# wireless-ac-motor-controller-mk-1_2.net
KiCad netlist of a schematic drawn in EAGLE
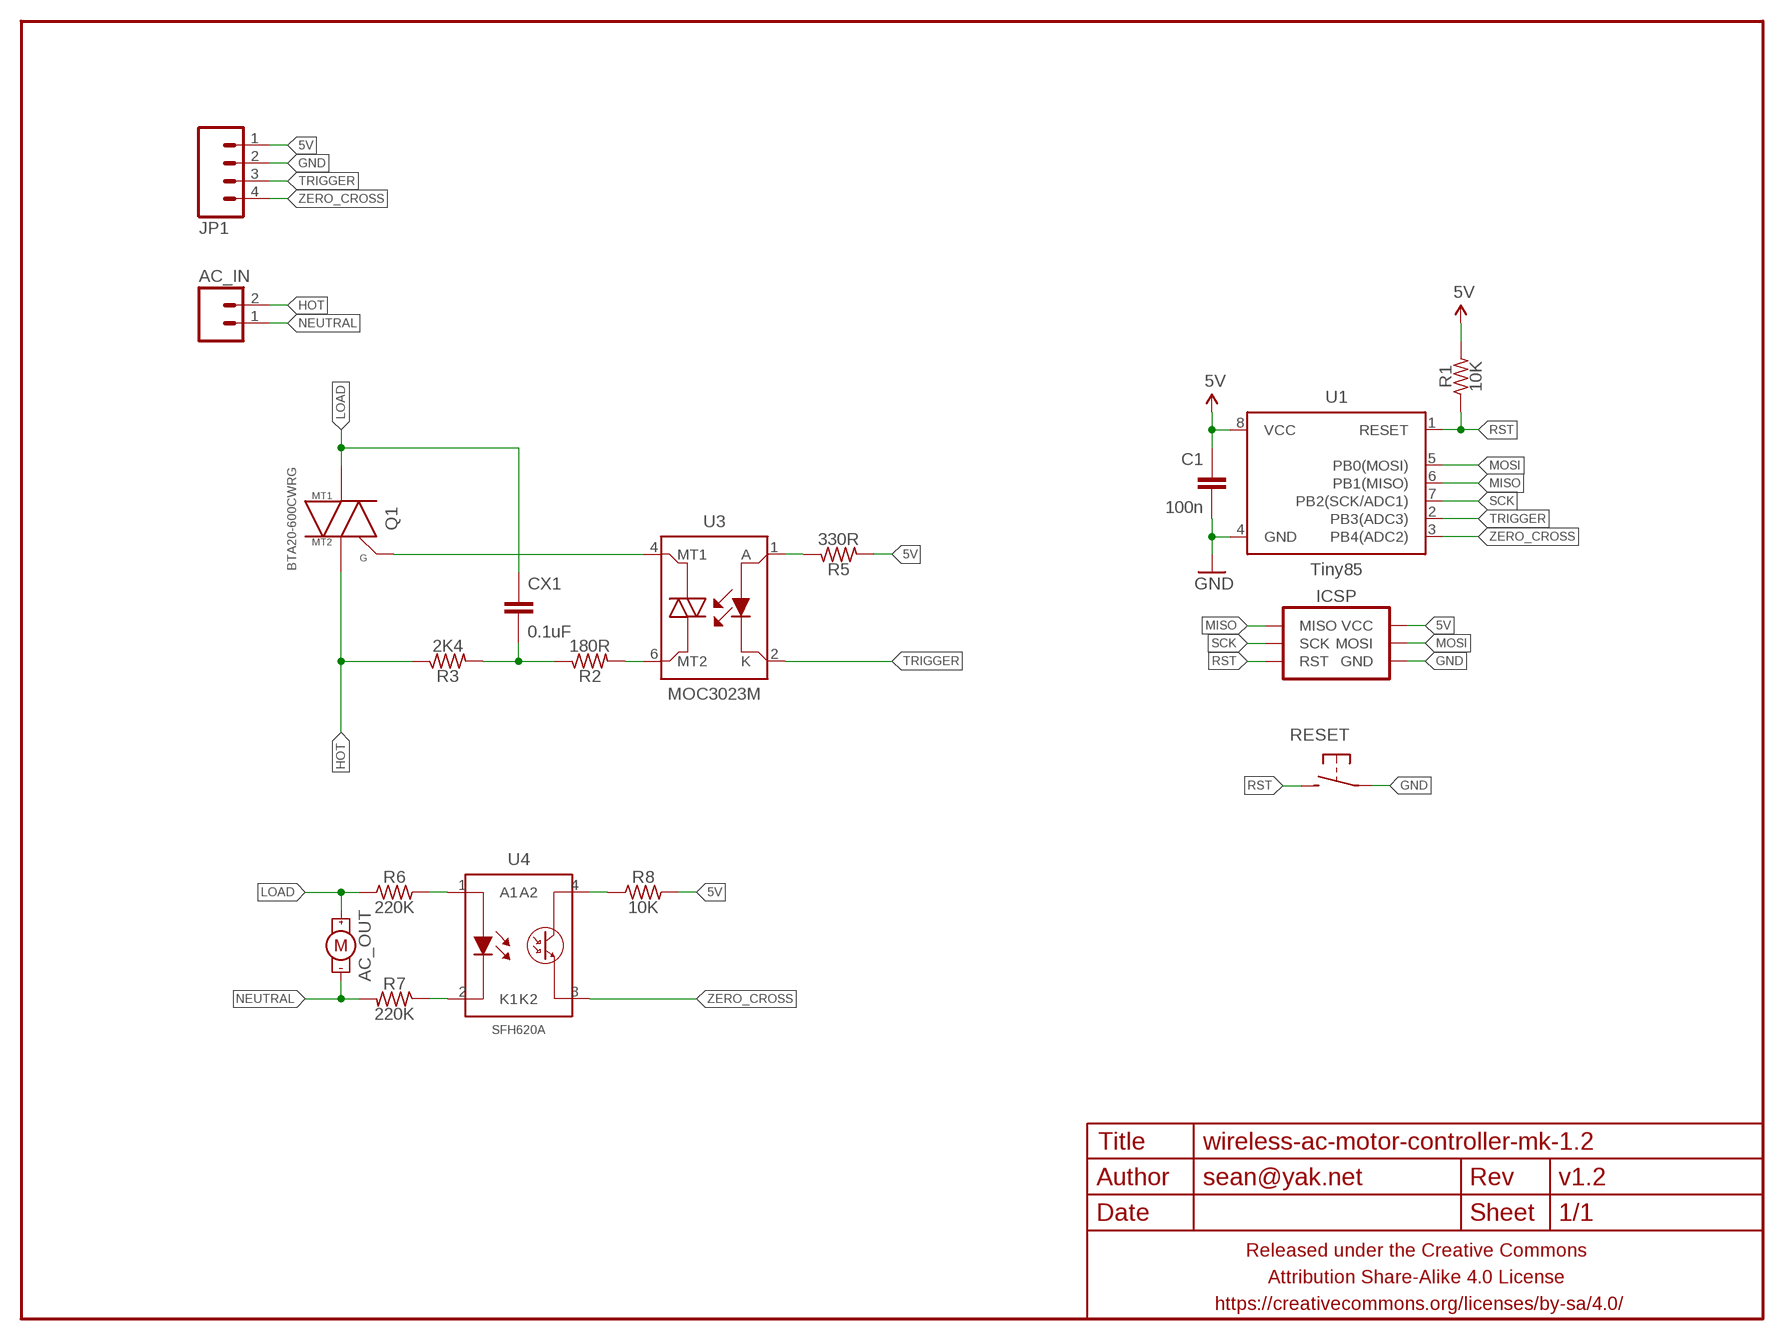
[diagram p0: schematic, sheet 1]

(export (version "E")
  (design (tool "Eeschema 10.0.6"))
  (components
    (comp (ref "AC_IN")
      (value "SCREWTERMINAL-25MM")
      (footprint "eagle-import:SCREWTERM-5MM-2")
      (libsource (lib "eagle-import") (part "SCREWTERMINAL-25MM"))
    )
    (comp (ref "AC_OUT")
      (value "MOTOR5MM-SCREW-TERM")
      (footprint "eagle-import:1X02_5MM_SCREW")
      (libsource (lib "eagle-import") (part "MOTOR5MM-SCREW-TERM"))
    )
    (comp (ref "C1")
      (value "100n")
      (footprint "eagle-import:C0805")
      (libsource (lib "eagle-import") (part "CAPACITOR-CERAMICC0805"))
    )
    (comp (ref "CX1")
      (value "0.1uF")
      (footprint "eagle-import:XC10B6")
      (libsource (lib "eagle-import") (part "CXXC10B6"))
    )
    (comp (ref "FRAME1")
      (value "FRAME-LETTERNO_PACKAGE")
      (footprint "eagle-import:DUMMY")
      (fields (field (name "DESIGNER") "sean@yak.net") (field (name "VERSION") "v1.2"))
      (libsource (lib "eagle-import") (part "FRAME-LETTERNO_PACKAGE"))
    )
    (comp (ref "ICSP")
      (value "AVR_SPI_PRG_6PTH")
      (footprint "eagle-import:2X3")
      (libsource (lib "eagle-import") (part "AVR_SPI_PRG_6PTH"))
    )
    (comp (ref "JP1")
      (value "M04JST-PTH-VERT")
      (footprint "eagle-import:JST-4-PH-VERT-PTH")
      (libsource (lib "eagle-import") (part "M04JST-PTH-VERT"))
    )
    (comp (ref "Q1")
      (value "BTA20-600CWRG")
      (footprint "eagle-import:TO220V")
      (libsource (lib "eagle-import") (part "TRIACTO-220-VERT"))
    )
    (comp (ref "R1")
      (value "10K")
      (footprint "eagle-import:R0805")
      (libsource (lib "eagle-import") (part "RESISTORR0805"))
    )
    (comp (ref "R2")
      (value "180R")
      (footprint "eagle-import:R0805")
      (libsource (lib "eagle-import") (part "RESISTORR0805"))
    )
    (comp (ref "R3")
      (value "2K4")
      (footprint "eagle-import:R0805")
      (libsource (lib "eagle-import") (part "RESISTORR0805"))
    )
    (comp (ref "R5")
      (value "330R")
      (footprint "eagle-import:R0805")
      (libsource (lib "eagle-import") (part "RESISTORR0805"))
    )
    (comp (ref "R6")
      (value "220K")
      (footprint "eagle-import:0411V")
      (libsource (lib "eagle-import") (part "RESISTOR0411/3V"))
    )
    (comp (ref "R7")
      (value "220K")
      (footprint "eagle-import:0411V")
      (libsource (lib "eagle-import") (part "RESISTOR0411/3V"))
    )
    (comp (ref "R8")
      (value "10K")
      (footprint "eagle-import:R0805")
      (libsource (lib "eagle-import") (part "RESISTORR0805"))
    )
    (comp (ref "RESET")
      (value "SPST-NO-TACT3MM-PTH-SMALL-PADS")
      (footprint "eagle-import:DTS-3-SMALL-PADS")
      (libsource (lib "eagle-import") (part "SPST-NO-TACT3MM-PTH-SMALL-PADS"))
    )
    (comp (ref "U1")
      (value "Tiny85")
      (footprint "eagle-import:SO08-EIAJ")
      (libsource (lib "eagle-import") (part "ATTINY45TINY85-20-SOICW"))
    )
    (comp (ref "U3")
      (value "MOC3023M")
      (footprint "eagle-import:DIP06")
      (libsource (lib "eagle-import") (part "MOC30XXMOC30XXM-DIP6"))
    )
    (comp (ref "U4")
      (value "SFH620A")
      (footprint "eagle-import:DIL04")
      (libsource (lib "eagle-import") (part "OPTOISOLATORDIP4"))
    )
  )
  (nets
    (net (code "1") (name "5V") (class "Default")
      (node (ref "C1") (pin "1") (pinfunction "1_1") (pintype "passive"))
      (node (ref "ICSP") (pin "2") (pinfunction "VCC_2") (pintype "passive"))
      (node (ref "JP1") (pin "1") (pinfunction "1_1") (pintype "passive"))
      (node (ref "R1") (pin "2") (pinfunction "2_2") (pintype "passive"))
      (node (ref "R5") (pin "2") (pinfunction "2_2") (pintype "passive"))
      (node (ref "R8") (pin "2") (pinfunction "2_2") (pintype "passive"))
      (node (ref "U1") (pin "8") (pinfunction "VCC_8") (pintype "bidirectional"))
    )
    (net (code "2") (name "GND") (class "Default")
      (node (ref "C1") (pin "2") (pinfunction "2_2") (pintype "passive"))
      (node (ref "ICSP") (pin "6") (pinfunction "GND_6") (pintype "passive"))
      (node (ref "JP1") (pin "2") (pinfunction "2_2") (pintype "passive"))
      (node (ref "RESET") (pin "1") (pinfunction "1_1") (pintype "passive"))
      (node (ref "U1") (pin "4") (pinfunction "GND_4") (pintype "bidirectional"))
    )
    (net (code "3") (name "HOT") (class "Default")
      (node (ref "AC_IN") (pin "2") (pinfunction "2_2") (pintype "passive"))
      (node (ref "Q1") (pin "2") (pinfunction "MT2_2") (pintype "bidirectional"))
      (node (ref "R3") (pin "1") (pinfunction "1_1") (pintype "passive"))
    )
    (net (code "4") (name "LOAD") (class "Default")
      (node (ref "AC_OUT") (pin "1") (pinfunction "+_1") (pintype "bidirectional"))
      (node (ref "CX1") (pin "1") (pinfunction "1_1") (pintype "passive"))
      (node (ref "Q1") (pin "1") (pinfunction "MT1_1") (pintype "bidirectional"))
      (node (ref "R6") (pin "1") (pinfunction "1_1") (pintype "passive"))
    )
    (net (code "5") (name "MISO") (class "Default")
      (node (ref "ICSP") (pin "1") (pinfunction "MISO_1") (pintype "passive"))
      (node (ref "U1") (pin "6") (pinfunction "PB1(MISO)_6") (pintype "bidirectional"))
    )
    (net (code "6") (name "MOSI") (class "Default")
      (node (ref "ICSP") (pin "4") (pinfunction "MOSI_4") (pintype "passive"))
      (node (ref "U1") (pin "5") (pinfunction "PB0(MOSI)_5") (pintype "bidirectional"))
    )
    (net (code "7") (name "NEUTRAL") (class "Default")
      (node (ref "AC_IN") (pin "1") (pinfunction "1_1") (pintype "passive"))
      (node (ref "AC_OUT") (pin "2") (pinfunction "-_2") (pintype "bidirectional"))
      (node (ref "R7") (pin "2") (pinfunction "2_2") (pintype "passive"))
    )
    (net (code "8") (name "Net-(CX1-Pad2)") (class "Default")
      (node (ref "CX1") (pin "2") (pinfunction "2_2") (pintype "passive"))
      (node (ref "R2") (pin "1") (pinfunction "1_1") (pintype "passive"))
      (node (ref "R3") (pin "2") (pinfunction "2_2") (pintype "passive"))
    )
    (net (code "9") (name "Net-(Q1-GATE)") (class "Default")
      (node (ref "Q1") (pin "3") (pinfunction "GATE_3") (pintype "bidirectional"))
      (node (ref "U3") (pin "4") (pinfunction "MT1_4") (pintype "bidirectional"))
    )
    (net (code "10") (name "Net-(U3-A)") (class "Default")
      (node (ref "R5") (pin "1") (pinfunction "1_1") (pintype "passive"))
      (node (ref "U3") (pin "1") (pinfunction "A_1") (pintype "bidirectional"))
    )
    (net (code "11") (name "Net-(U3-MT2)") (class "Default")
      (node (ref "R2") (pin "2") (pinfunction "2_2") (pintype "passive"))
      (node (ref "U3") (pin "6") (pinfunction "MT2_6") (pintype "bidirectional"))
    )
    (net (code "12") (name "Net-(U4-A1)") (class "Default")
      (node (ref "R6") (pin "2") (pinfunction "2_2") (pintype "passive"))
      (node (ref "U4") (pin "1") (pinfunction "A1_1") (pintype "bidirectional"))
    )
    (net (code "13") (name "Net-(U4-A2)") (class "Default")
      (node (ref "R8") (pin "1") (pinfunction "1_1") (pintype "passive"))
      (node (ref "U4") (pin "4") (pinfunction "A2_4") (pintype "bidirectional"))
    )
    (net (code "14") (name "Net-(U4-K1)") (class "Default")
      (node (ref "R7") (pin "1") (pinfunction "1_1") (pintype "passive"))
      (node (ref "U4") (pin "2") (pinfunction "K1_2") (pintype "bidirectional"))
    )
    (net (code "15") (name "RST") (class "Default")
      (node (ref "ICSP") (pin "5") (pinfunction "RST_5") (pintype "passive"))
      (node (ref "R1") (pin "1") (pinfunction "1_1") (pintype "passive"))
      (node (ref "RESET") (pin "2") (pinfunction "2_2") (pintype "passive"))
      (node (ref "U1") (pin "1") (pinfunction "RESET_1") (pintype "bidirectional"))
    )
    (net (code "16") (name "SCK") (class "Default")
      (node (ref "ICSP") (pin "3") (pinfunction "SCK_3") (pintype "passive"))
      (node (ref "U1") (pin "7") (pinfunction "PB2(SCK/ADC1)_7") (pintype "bidirectional"))
    )
    (net (code "17") (name "TRIGGER") (class "Default")
      (node (ref "JP1") (pin "3") (pinfunction "3_3") (pintype "passive"))
      (node (ref "U1") (pin "2") (pinfunction "PB3(ADC3)_2") (pintype "bidirectional"))
      (node (ref "U3") (pin "2") (pinfunction "K_2") (pintype "bidirectional"))
    )
    (net (code "18") (name "ZERO_CROSS") (class "Default")
      (node (ref "JP1") (pin "4") (pinfunction "4_4") (pintype "passive"))
      (node (ref "U1") (pin "3") (pinfunction "PB4(ADC2)_3") (pintype "bidirectional"))
      (node (ref "U4") (pin "3") (pinfunction "K2_3") (pintype "bidirectional"))
    )
  )
)
